# target.net
KiCad netlist of a schematic drawn in Altium Designer
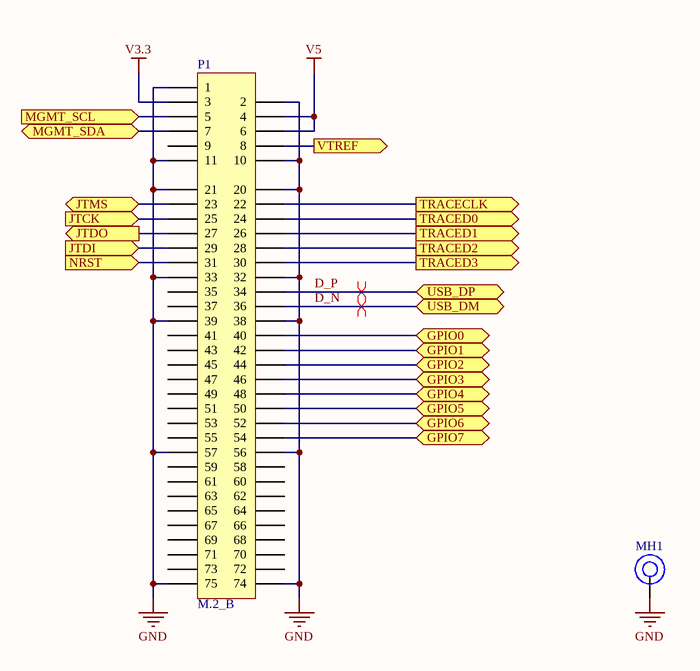
[diagram p0: target.SchDoc]

(export (version "E")
  (design (tool "Eeschema 10.0.6"))
  (components
    (comp (ref "MH1")
      (value "Mounting_Hole")
      (footprint "WA-SMSI_M2.5")
      (libsource (lib "misc") (part "Mounting_Hole"))
    )
    (comp (ref "P1") (value "M.2_B") (footprint "M.2_B") (libsource (lib "misc") (part "M.2_B")))
  )
  (nets
    (net (code "1") (name "/D_N") (class "Default")
      (node (ref "P1") (pin "36") (pinfunction "36_36") (pintype "passive"))
    )
    (net (code "2") (name "/D_P") (class "Default")
      (node (ref "P1") (pin "34") (pinfunction "34_34") (pintype "passive"))
    )
    (net (code "3") (name "/GPIO0") (class "Default")
      (node (ref "P1") (pin "40") (pinfunction "40_40") (pintype "passive"))
    )
    (net (code "4") (name "/GPIO1") (class "Default")
      (node (ref "P1") (pin "42") (pinfunction "42_42") (pintype "passive"))
    )
    (net (code "5") (name "/GPIO2") (class "Default")
      (node (ref "P1") (pin "44") (pinfunction "44_44") (pintype "passive"))
    )
    (net (code "6") (name "/GPIO3") (class "Default")
      (node (ref "P1") (pin "46") (pinfunction "46_46") (pintype "passive"))
    )
    (net (code "7") (name "/GPIO4") (class "Default")
      (node (ref "P1") (pin "48") (pinfunction "48_48") (pintype "passive"))
    )
    (net (code "8") (name "/GPIO5") (class "Default")
      (node (ref "P1") (pin "50") (pinfunction "50_50") (pintype "passive"))
    )
    (net (code "9") (name "/GPIO6") (class "Default")
      (node (ref "P1") (pin "52") (pinfunction "52_52") (pintype "passive"))
    )
    (net (code "10") (name "/GPIO7") (class "Default")
      (node (ref "P1") (pin "54") (pinfunction "54_54") (pintype "passive"))
    )
    (net (code "11") (name "/JTCK") (class "Default")
      (node (ref "P1") (pin "25") (pinfunction "25_25") (pintype "passive"))
    )
    (net (code "12") (name "/JTDI") (class "Default")
      (node (ref "P1") (pin "29") (pinfunction "29_29") (pintype "passive"))
    )
    (net (code "13") (name "/JTDO") (class "Default")
      (node (ref "P1") (pin "27") (pinfunction "27_27") (pintype "passive"))
    )
    (net (code "14") (name "/JTMS") (class "Default")
      (node (ref "P1") (pin "23") (pinfunction "23_23") (pintype "passive"))
    )
    (net (code "15") (name "/MGMT_SCL") (class "Default")
      (node (ref "P1") (pin "5") (pinfunction "5_5") (pintype "passive"))
    )
    (net (code "16") (name "/MGMT_SDA") (class "Default")
      (node (ref "P1") (pin "7") (pinfunction "7_7") (pintype "passive"))
    )
    (net (code "17") (name "/NRST") (class "Default")
      (node (ref "P1") (pin "31") (pinfunction "31_31") (pintype "passive"))
    )
    (net (code "18") (name "/TRACECLK") (class "Default")
      (node (ref "P1") (pin "22") (pinfunction "22_22") (pintype "passive"))
    )
    (net (code "19") (name "/TRACED0") (class "Default")
      (node (ref "P1") (pin "24") (pinfunction "24_24") (pintype "passive"))
    )
    (net (code "20") (name "/TRACED1") (class "Default")
      (node (ref "P1") (pin "26") (pinfunction "26_26") (pintype "passive"))
    )
    (net (code "21") (name "/TRACED2") (class "Default")
      (node (ref "P1") (pin "28") (pinfunction "28_28") (pintype "passive"))
    )
    (net (code "22") (name "/TRACED3") (class "Default")
      (node (ref "P1") (pin "30") (pinfunction "30_30") (pintype "passive"))
    )
    (net (code "23") (name "/VTREF") (class "Default")
      (node (ref "P1") (pin "8") (pinfunction "8_8") (pintype "passive"))
    )
    (net (code "24") (name "GND") (class "Default")
      (node (ref "MH1") (pin "1") (pintype "passive"))
      (node (ref "P1") (pin "1") (pinfunction "1_1") (pintype "passive"))
      (node (ref "P1") (pin "10") (pinfunction "10_10") (pintype "passive"))
      (node (ref "P1") (pin "11") (pinfunction "11_11") (pintype "passive"))
      (node (ref "P1") (pin "2") (pinfunction "2_2") (pintype "passive"))
      (node (ref "P1") (pin "20") (pinfunction "20_20") (pintype "passive"))
      (node (ref "P1") (pin "21") (pinfunction "21_21") (pintype "passive"))
      (node (ref "P1") (pin "32") (pinfunction "32_32") (pintype "passive"))
      (node (ref "P1") (pin "33") (pinfunction "33_33") (pintype "passive"))
      (node (ref "P1") (pin "38") (pinfunction "38_38") (pintype "passive"))
      (node (ref "P1") (pin "39") (pinfunction "39_39") (pintype "passive"))
      (node (ref "P1") (pin "56") (pinfunction "56_56") (pintype "passive"))
      (node (ref "P1") (pin "57") (pinfunction "57_57") (pintype "passive"))
      (node (ref "P1") (pin "74") (pinfunction "74_74") (pintype "passive"))
      (node (ref "P1") (pin "75") (pinfunction "75_75") (pintype "passive"))
    )
    (net (code "25") (name "V3.3") (class "Default")
      (node (ref "P1") (pin "3") (pinfunction "3_3") (pintype "passive"))
    )
    (net (code "26") (name "V5") (class "Default")
      (node (ref "P1") (pin "4") (pinfunction "4_4") (pintype "passive"))
      (node (ref "P1") (pin "6") (pinfunction "6_6") (pintype "passive"))
    )
    (net (code "27") (name "unconnected-(P1-Pad9)") (class "Default")
      (node (ref "P1") (pin "9") (pinfunction "9_9") (pintype "passive"))
    )
    (net (code "28") (name "unconnected-(P1-Pad35)") (class "Default")
      (node (ref "P1") (pin "35") (pinfunction "35_35") (pintype "passive"))
    )
    (net (code "29") (name "unconnected-(P1-Pad37)") (class "Default")
      (node (ref "P1") (pin "37") (pinfunction "37_37") (pintype "passive"))
    )
    (net (code "30") (name "unconnected-(P1-Pad41)") (class "Default")
      (node (ref "P1") (pin "41") (pinfunction "41_41") (pintype "passive"))
    )
    (net (code "31") (name "unconnected-(P1-Pad43)") (class "Default")
      (node (ref "P1") (pin "43") (pinfunction "43_43") (pintype "passive"))
    )
    (net (code "32") (name "unconnected-(P1-Pad45)") (class "Default")
      (node (ref "P1") (pin "45") (pinfunction "45_45") (pintype "passive"))
    )
    (net (code "33") (name "unconnected-(P1-Pad47)") (class "Default")
      (node (ref "P1") (pin "47") (pinfunction "47_47") (pintype "passive"))
    )
    (net (code "34") (name "unconnected-(P1-Pad49)") (class "Default")
      (node (ref "P1") (pin "49") (pinfunction "49_49") (pintype "passive"))
    )
    (net (code "35") (name "unconnected-(P1-Pad51)") (class "Default")
      (node (ref "P1") (pin "51") (pinfunction "51_51") (pintype "passive"))
    )
    (net (code "36") (name "unconnected-(P1-Pad53)") (class "Default")
      (node (ref "P1") (pin "53") (pinfunction "53_53") (pintype "passive"))
    )
    (net (code "37") (name "unconnected-(P1-Pad55)") (class "Default")
      (node (ref "P1") (pin "55") (pinfunction "55_55") (pintype "passive"))
    )
    (net (code "38") (name "unconnected-(P1-Pad58)") (class "Default")
      (node (ref "P1") (pin "58") (pinfunction "58_58") (pintype "passive"))
    )
    (net (code "39") (name "unconnected-(P1-Pad59)") (class "Default")
      (node (ref "P1") (pin "59") (pinfunction "59_59") (pintype "passive"))
    )
    (net (code "40") (name "unconnected-(P1-Pad60)") (class "Default")
      (node (ref "P1") (pin "60") (pinfunction "60_60") (pintype "passive"))
    )
    (net (code "41") (name "unconnected-(P1-Pad61)") (class "Default")
      (node (ref "P1") (pin "61") (pinfunction "61_61") (pintype "passive"))
    )
    (net (code "42") (name "unconnected-(P1-Pad62)") (class "Default")
      (node (ref "P1") (pin "62") (pinfunction "62_62") (pintype "passive"))
    )
    (net (code "43") (name "unconnected-(P1-Pad63)") (class "Default")
      (node (ref "P1") (pin "63") (pinfunction "63_63") (pintype "passive"))
    )
    (net (code "44") (name "unconnected-(P1-Pad64)") (class "Default")
      (node (ref "P1") (pin "64") (pinfunction "64_64") (pintype "passive"))
    )
    (net (code "45") (name "unconnected-(P1-Pad65)") (class "Default")
      (node (ref "P1") (pin "65") (pinfunction "65_65") (pintype "passive"))
    )
    (net (code "46") (name "unconnected-(P1-Pad66)") (class "Default")
      (node (ref "P1") (pin "66") (pinfunction "66_66") (pintype "passive"))
    )
    (net (code "47") (name "unconnected-(P1-Pad67)") (class "Default")
      (node (ref "P1") (pin "67") (pinfunction "67_67") (pintype "passive"))
    )
    (net (code "48") (name "unconnected-(P1-Pad68)") (class "Default")
      (node (ref "P1") (pin "68") (pinfunction "68_68") (pintype "passive"))
    )
    (net (code "49") (name "unconnected-(P1-Pad69)") (class "Default")
      (node (ref "P1") (pin "69") (pinfunction "69_69") (pintype "passive"))
    )
    (net (code "50") (name "unconnected-(P1-Pad70)") (class "Default")
      (node (ref "P1") (pin "70") (pinfunction "70_70") (pintype "passive"))
    )
    (net (code "51") (name "unconnected-(P1-Pad71)") (class "Default")
      (node (ref "P1") (pin "71") (pinfunction "71_71") (pintype "passive"))
    )
    (net (code "52") (name "unconnected-(P1-Pad72)") (class "Default")
      (node (ref "P1") (pin "72") (pinfunction "72_72") (pintype "passive"))
    )
    (net (code "53") (name "unconnected-(P1-Pad73)") (class "Default")
      (node (ref "P1") (pin "73") (pinfunction "73_73") (pintype "passive"))
    )
  )
)
